# POWER.net
KiCad netlist of a schematic drawn in Altium Designer
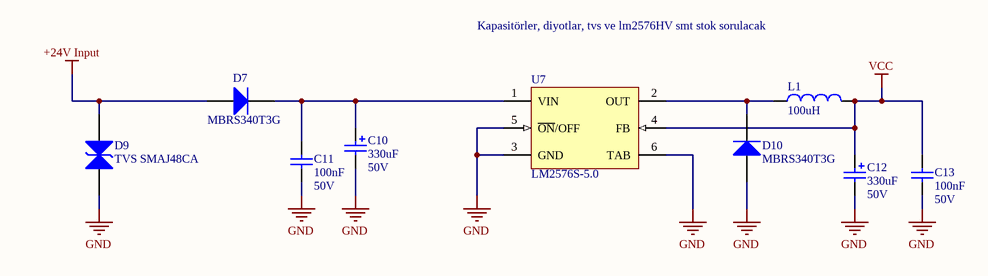
[diagram p0: POWER.SchDoc]

(export (version "E")
  (design (tool "Eeschema 10.0.6"))
  (components
    (comp (ref "C10")
      (value "330uF")
      (footprint "CAP Size H13= 12.5x13.8mm")
      (description "Polarized Capacitor (Radial)")
      (fields
        (field (name "VOLTAGE") "50V")
        (field (name "Comment") "Cap Pol1")
        (field (name "PUBLISHER") "Altium Limited")
      )
      (libsource (lib "Erdem_05112012") (part "Cap Pol1"))
    )
    (comp (ref "C11")
      (value "100nF")
      (footprint "3-0603_L")
      (description "Capacitor")
      (fields
        (field (name "VOLTAGE") "50V")
        (field (name "Comment") "Cap")
        (field (name "PUBLISHER") "Altium Limited")
      )
      (libsource (lib "Erdem_05112012") (part "Cap"))
    )
    (comp (ref "C12")
      (value "330uF")
      (footprint "CAP Size H13= 12.5x13.8mm")
      (description "Polarized Capacitor (Radial)")
      (fields
        (field (name "VOLTAGE") "50V")
        (field (name "Comment") "Cap Pol1")
        (field (name "PUBLISHER") "Altium Limited")
      )
      (libsource (lib "Erdem_05112012") (part "Cap Pol1"))
    )
    (comp (ref "C13")
      (value "100nF")
      (footprint "3-0603_L")
      (description "Capacitor")
      (fields
        (field (name "VOLTAGE") "50V")
        (field (name "Comment") "Cap")
        (field (name "PUBLISHER") "Altium Limited")
      )
      (libsource (lib "Erdem_05112012") (part "Cap"))
    )
    (comp (ref "D7")
      (value "MBRS340T3G")
      (footprint "CASE 403-03 ISSUE E")
      (description "3 Amp Shotky Rectifier")
      (fields (field (name "PUBLISHER") "Altium Limited"))
      (libsource (lib "Erdem_05112012") (part "MBRS340T3G"))
    )
    (comp (ref "D9")
      (value "TVS SMAJ48CA")
      (footprint "DO214 AA")
      (fields (field (name "PUBLISHER") "Altium Limited"))
      (libsource (lib "Erdem_05112012") (part "TVS SMAJ48CA"))
    )
    (comp (ref "D10")
      (value "MBRS340T3G")
      (footprint "CASE 403-03 ISSUE E")
      (description "3 Amp Shotky Rectifier")
      (fields (field (name "PUBLISHER") "Altium Limited"))
      (libsource (lib "Erdem_05112012") (part "MBRS340T3G"))
    )
    (comp (ref "L1")
      (value "100uH")
      (footprint "EB-221M18G01")
      (description "Inductor")
      (fields (field (name "PUBLISHER") "Altium Limited"))
      (libsource (lib "Erdem_05112012") (part "Inductor"))
    )
    (comp (ref "U7")
      (value "LM2576S-5.0")
      (footprint "TS5B_M")
      (description "SIMPLE SWITCHER; 3A Step-Down Voltage Regulator")
      (fields
        (field (name "MANUFACTURER") "National Semiconductor")
        (field (name "DIGIKEYPARTNUMBER") "LM2576S-5.0-ND")
        (field (name "PUBLISHER") "Altium Limited")
      )
      (libsource (lib "Erdem_05112012") (part "LM2576S-5.0"))
    )
  )
  (nets
    (net (code "1") (name "+24V Input") (class "Default")
      (node (ref "D7") (pin "1") (pinfunction "A_1") (pintype "passive"))
      (node (ref "D9") (pin "2") (pinfunction "2_2") (pintype "passive"))
    )
    (net (code "2") (name "GND") (class "Default")
      (node (ref "C10") (pin "2") (pinfunction "2_2") (pintype "passive"))
      (node (ref "C11") (pin "1") (pinfunction "1_1") (pintype "passive"))
      (node (ref "C12") (pin "2") (pinfunction "2_2") (pintype "passive"))
      (node (ref "C13") (pin "1") (pinfunction "1_1") (pintype "passive"))
      (node (ref "D10") (pin "1") (pinfunction "A_1") (pintype "passive"))
      (node (ref "D9") (pin "1") (pinfunction "1_1") (pintype "passive"))
      (node (ref "U7") (pin "3") (pinfunction "GND_3") (pintype "power_in"))
      (node (ref "U7") (pin "5") (pinfunction "~{ON}/OFF_5") (pintype "input"))
      (node (ref "U7") (pin "6") (pinfunction "TAB_6") (pintype "power_in"))
    )
    (net (code "3") (name "Net-(D7-K)") (class "Default")
      (node (ref "C10") (pin "1") (pinfunction "1_1") (pintype "passive"))
      (node (ref "C11") (pin "2") (pinfunction "2_2") (pintype "passive"))
      (node (ref "D7") (pin "2") (pinfunction "K_2") (pintype "passive"))
      (node (ref "U7") (pin "1") (pinfunction "VIN_1") (pintype "power_in"))
    )
    (net (code "4") (name "Net-(D10-K)") (class "Default")
      (node (ref "D10") (pin "2") (pinfunction "K_2") (pintype "passive"))
      (node (ref "L1") (pin "1") (pinfunction "1_1") (pintype "passive"))
      (node (ref "U7") (pin "2") (pinfunction "OUT_2") (pintype "power_in"))
    )
    (net (code "5") (name "VCC") (class "Default")
      (node (ref "C12") (pin "1") (pinfunction "1_1") (pintype "passive"))
      (node (ref "C13") (pin "2") (pinfunction "2_2") (pintype "passive"))
      (node (ref "L1") (pin "2") (pinfunction "2_2") (pintype "passive"))
      (node (ref "U7") (pin "4") (pinfunction "FB_4") (pintype "input"))
    )
  )
)
